# main.net
KiCad netlist of a schematic drawn in Altium Designer
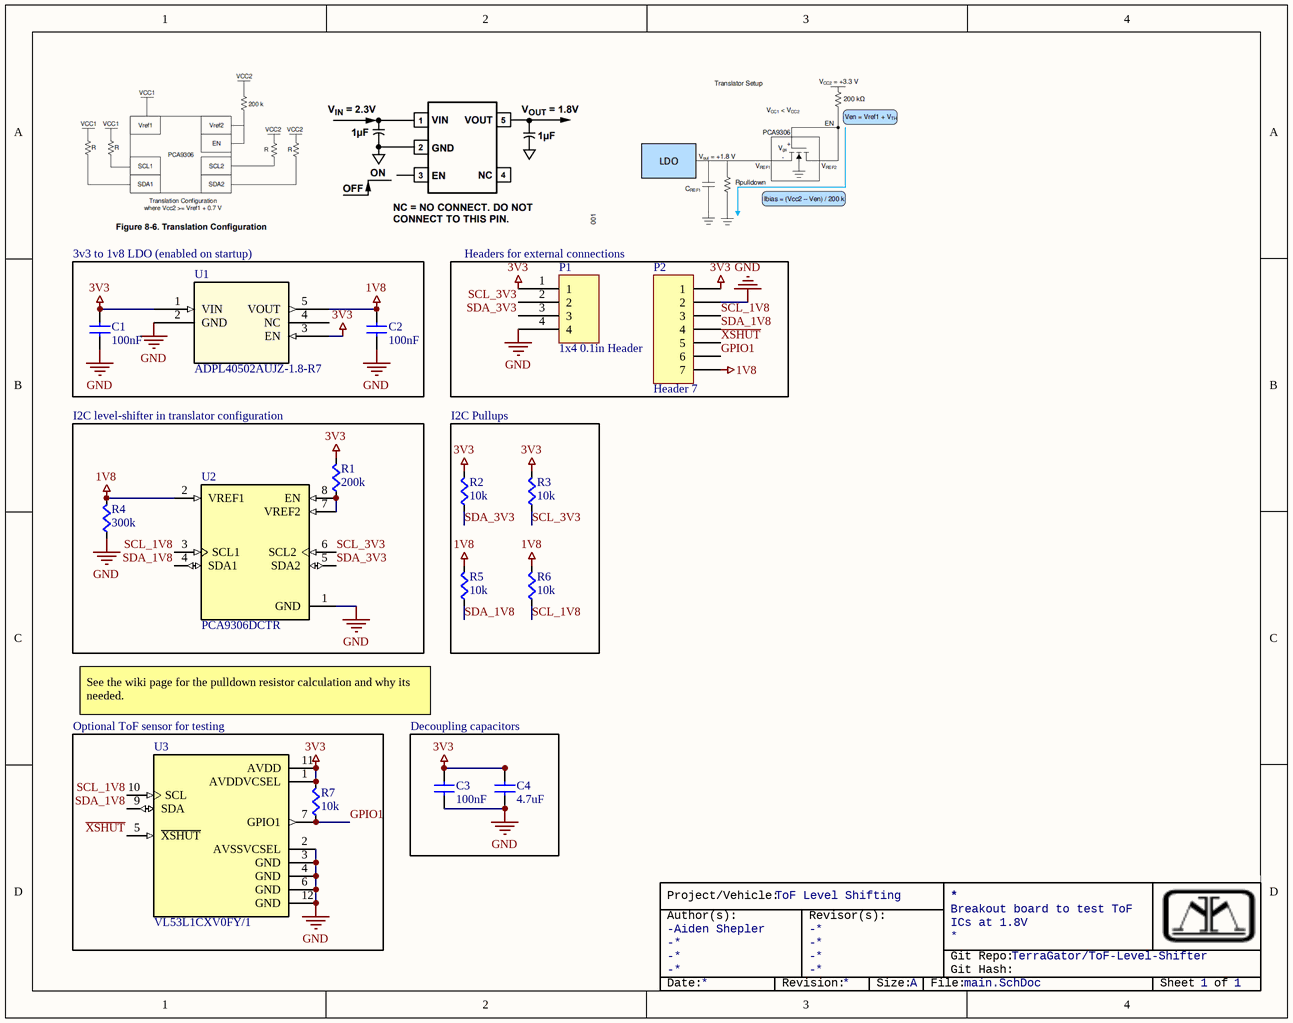
[diagram p0: main.SchDoc]

(export (version "E")
  (design (tool "Eeschema 10.0.6"))
  (components
    (comp (ref "C1")
      (value "100nF")
      (footprint "CAPC0603")
      (fields (field (name "Comment") "Cap"))
      (libsource (lib "Passives") (part "Cap"))
    )
    (comp (ref "C2")
      (value "100nF")
      (footprint "CAPC0603")
      (fields (field (name "Comment") "Cap"))
      (libsource (lib "Passives") (part "Cap"))
    )
    (comp (ref "C3")
      (value "100nF")
      (footprint "CAPC0603")
      (fields (field (name "Comment") "Cap"))
      (libsource (lib "Passives") (part "Cap"))
    )
    (comp (ref "C4")
      (value "4.7uF")
      (footprint "CAPC0603")
      (fields (field (name "Comment") "Cap"))
      (libsource (lib "Passives") (part "Cap"))
    )
    (comp (ref "P1")
      (value "1x4 0.1in Header")
      (footprint "1x4 0.1in Header")
      (libsource (lib "Connectors") (part "1x4 0.1in Header"))
    )
    (comp (ref "P2")
      (value "Header 7")
      (footprint "HDR1X7")
      (description "Header, 7-Pin")
      (fields (field (name "PUBLISHER") "Altium Limited"))
      (libsource (lib "Miscellaneous Connectors") (part "Header 7"))
    )
    (comp (ref "R1")
      (value "200k")
      (footprint "RES0603")
      (description "SMD, RES0603")
      (fields (field (name "Comment") "Res"))
      (libsource (lib "Passives") (part "Res"))
    )
    (comp (ref "R2")
      (value "10k")
      (footprint "RES0603")
      (description "SMD, RES0603")
      (fields (field (name "Comment") "Res"))
      (libsource (lib "Passives") (part "Res"))
    )
    (comp (ref "R3")
      (value "10k")
      (footprint "RES0603")
      (description "SMD, RES0603")
      (fields (field (name "Comment") "Res"))
      (libsource (lib "Passives") (part "Res"))
    )
    (comp (ref "R4")
      (value "300k")
      (footprint "RES0603")
      (description "SMD, RES0603")
      (fields (field (name "Comment") "Res"))
      (libsource (lib "Passives") (part "Res"))
    )
    (comp (ref "R5")
      (value "10k")
      (footprint "RES0603")
      (description "SMD, RES0603")
      (fields (field (name "Comment") "Res"))
      (libsource (lib "Passives") (part "Res"))
    )
    (comp (ref "R6")
      (value "10k")
      (footprint "RES0603")
      (description "SMD, RES0603")
      (fields (field (name "Comment") "Res"))
      (libsource (lib "Passives") (part "Res"))
    )
    (comp (ref "R7")
      (value "10k")
      (footprint "RES0603")
      (description "SMD, RES0603")
      (fields (field (name "Comment") "Res"))
      (libsource (lib "Passives") (part "Res"))
    )
    (comp (ref "U1")
      (value "ADPL40502AUJZ-1.8-R7")
      (footprint "TSOT-23-5_UJ-5_ADI")
      (description "Low Noise, 200mA, CMOS Linear Regulator (LDO)")
      (fields (field (name "COPYRIGHT") "Copyright (C) 2025 Ultra Librarian. All rights reserved."))
      (libsource (lib "Alexandria") (part "ADPL40502AUJZ-1.8-R7"))
    )
    (comp (ref "U2")
      (value "PCA9306DCTR")
      (footprint "SOP65P400X130-8N")
      (description "2-bit bidirectional 400-kHz I2C/SMBus voltage level translator")
      (fields (field (name "MF") "Texas Instruments"))
      (libsource (lib "Alexandria") (part "PCA9306DCTR"))
    )
    (comp (ref "U3")
      (value "VL53L1CXV0FY/1")
      (footprint "LGA-12 (VL53L1CXV0FY/1)")
      (description "ToF Optical Sensor 157.480 (4m) I²C Output from STMelectronics")
      (fields (field (name "MF") "STMicroelectronics"))
      (libsource (lib "Alexandria") (part "VL53L1CXV0FY/1"))
    )
  )
  (nets
    (net (code "1") (name "/GPIO1") (class "Default")
      (node (ref "P2") (pin "6") (pinfunction "6_6") (pintype "passive"))
      (node (ref "R7") (pin "2") (pinfunction "B_2") (pintype "passive"))
      (node (ref "U3") (pin "7") (pinfunction "GPIO1_7") (pintype "output"))
    )
    (net (code "2") (name "/SCL_1V8") (class "Default")
      (node (ref "P2") (pin "3") (pinfunction "3_3") (pintype "passive"))
      (node (ref "R6") (pin "2") (pinfunction "B_2") (pintype "passive"))
      (node (ref "U2") (pin "3") (pinfunction "SCL1_3") (pintype "input"))
      (node (ref "U3") (pin "10") (pinfunction "SCL_10") (pintype "input"))
    )
    (net (code "3") (name "/SCL_3V3") (class "Default")
      (node (ref "P1") (pin "2") (pinfunction "2_2") (pintype "passive"))
      (node (ref "R3") (pin "2") (pinfunction "B_2") (pintype "passive"))
      (node (ref "U2") (pin "6") (pinfunction "SCL2_6") (pintype "input"))
    )
    (net (code "4") (name "/SDA_1V8") (class "Default")
      (node (ref "P2") (pin "4") (pinfunction "4_4") (pintype "passive"))
      (node (ref "R5") (pin "2") (pinfunction "B_2") (pintype "passive"))
      (node (ref "U2") (pin "4") (pinfunction "SDA1_4") (pintype "bidirectional"))
      (node (ref "U3") (pin "9") (pinfunction "SDA_9") (pintype "bidirectional"))
    )
    (net (code "5") (name "/SDA_3V3") (class "Default")
      (node (ref "P1") (pin "3") (pinfunction "3_3") (pintype "passive"))
      (node (ref "R2") (pin "2") (pinfunction "B_2") (pintype "passive"))
      (node (ref "U2") (pin "5") (pinfunction "SDA2_5") (pintype "bidirectional"))
    )
    (net (code "6") (name "/~{XSHUT}") (class "Default")
      (node (ref "P2") (pin "5") (pinfunction "5_5") (pintype "passive"))
      (node (ref "U3") (pin "5") (pinfunction "~{XSHUT}_5") (pintype "input"))
    )
    (net (code "7") (name "1V8") (class "Default")
      (node (ref "C2") (pin "1") (pinfunction "A_1") (pintype "passive"))
      (node (ref "P2") (pin "7") (pinfunction "7_7") (pintype "passive"))
      (node (ref "R4") (pin "1") (pinfunction "A_1") (pintype "passive"))
      (node (ref "R5") (pin "1") (pinfunction "A_1") (pintype "passive"))
      (node (ref "R6") (pin "1") (pinfunction "A_1") (pintype "passive"))
      (node (ref "U1") (pin "5") (pinfunction "VOUT_5") (pintype "output"))
      (node (ref "U2") (pin "2") (pinfunction "VREF1_2") (pintype "input"))
    )
    (net (code "8") (name "3V3") (class "Default")
      (node (ref "C1") (pin "1") (pinfunction "A_1") (pintype "passive"))
      (node (ref "C3") (pin "1") (pinfunction "A_1") (pintype "passive"))
      (node (ref "C4") (pin "1") (pinfunction "A_1") (pintype "passive"))
      (node (ref "P1") (pin "1") (pinfunction "1_1") (pintype "passive"))
      (node (ref "P2") (pin "1") (pinfunction "1_1") (pintype "passive"))
      (node (ref "R1") (pin "1") (pinfunction "A_1") (pintype "passive"))
      (node (ref "R2") (pin "1") (pinfunction "A_1") (pintype "passive"))
      (node (ref "R3") (pin "1") (pinfunction "A_1") (pintype "passive"))
      (node (ref "R7") (pin "1") (pinfunction "A_1") (pintype "passive"))
      (node (ref "U1") (pin "1") (pinfunction "VIN_1") (pintype "input"))
      (node (ref "U1") (pin "3") (pinfunction "EN_3") (pintype "input"))
      (node (ref "U3") (pin "1") (pinfunction "AVDDVCSEL_1") (pintype "power_in"))
      (node (ref "U3") (pin "11") (pinfunction "AVDD_11") (pintype "power_in"))
    )
    (net (code "9") (name "GND") (class "Default")
      (node (ref "C1") (pin "2") (pinfunction "B_2") (pintype "passive"))
      (node (ref "C2") (pin "2") (pinfunction "B_2") (pintype "passive"))
      (node (ref "C3") (pin "2") (pinfunction "B_2") (pintype "passive"))
      (node (ref "C4") (pin "2") (pinfunction "B_2") (pintype "passive"))
      (node (ref "P1") (pin "4") (pinfunction "4_4") (pintype "passive"))
      (node (ref "P2") (pin "2") (pinfunction "2_2") (pintype "passive"))
      (node (ref "R4") (pin "2") (pinfunction "B_2") (pintype "passive"))
      (node (ref "U1") (pin "2") (pinfunction "GND_2") (pintype "power_in"))
      (node (ref "U2") (pin "1") (pinfunction "GND_1") (pintype "power_in"))
      (node (ref "U3") (pin "12") (pinfunction "GND_12") (pintype "power_in"))
      (node (ref "U3") (pin "2") (pinfunction "AVSSVCSEL_2") (pintype "power_in"))
      (node (ref "U3") (pin "3") (pinfunction "GND_3") (pintype "power_in"))
      (node (ref "U3") (pin "4") (pinfunction "GND_4") (pintype "power_in"))
      (node (ref "U3") (pin "6") (pinfunction "GND_6") (pintype "power_in"))
    )
    (net (code "10") (name "Net-(R1-B)") (class "Default")
      (node (ref "R1") (pin "2") (pinfunction "B_2") (pintype "passive"))
      (node (ref "U2") (pin "7") (pinfunction "VREF2_7") (pintype "input"))
      (node (ref "U2") (pin "8") (pinfunction "EN_8") (pintype "input"))
    )
    (net (code "11") (name "unconnected-(U1-NC-Pad4)") (class "Default")
      (node (ref "U1") (pin "4") (pinfunction "NC_4") (pintype "passive"))
    )
  )
)
